# A6SS-4.net
KiCad netlist of a schematic drawn in EAGLE
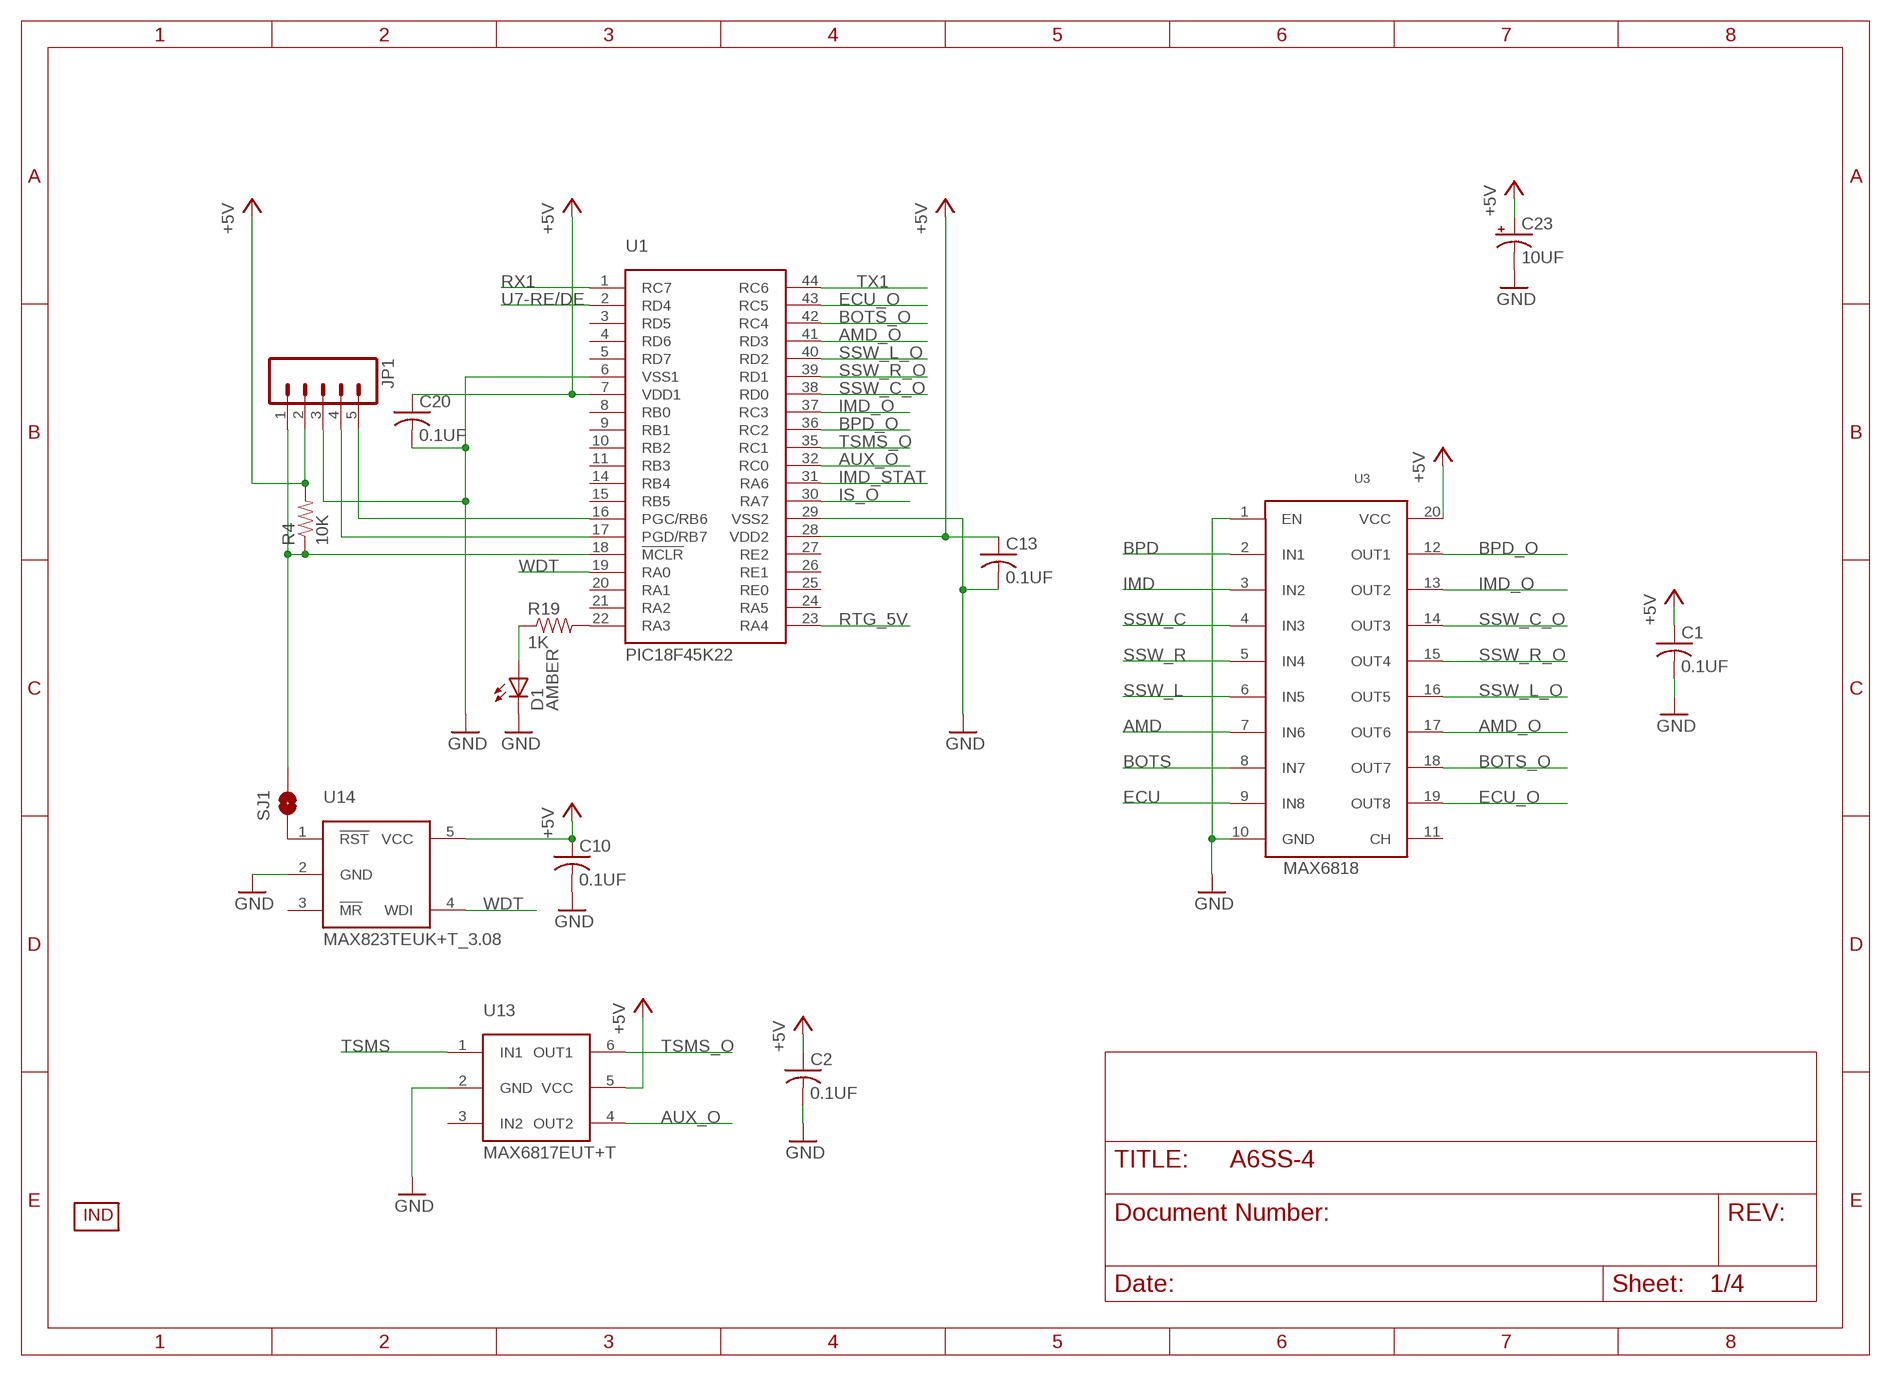
[diagram p0: schematic, sheet 1]
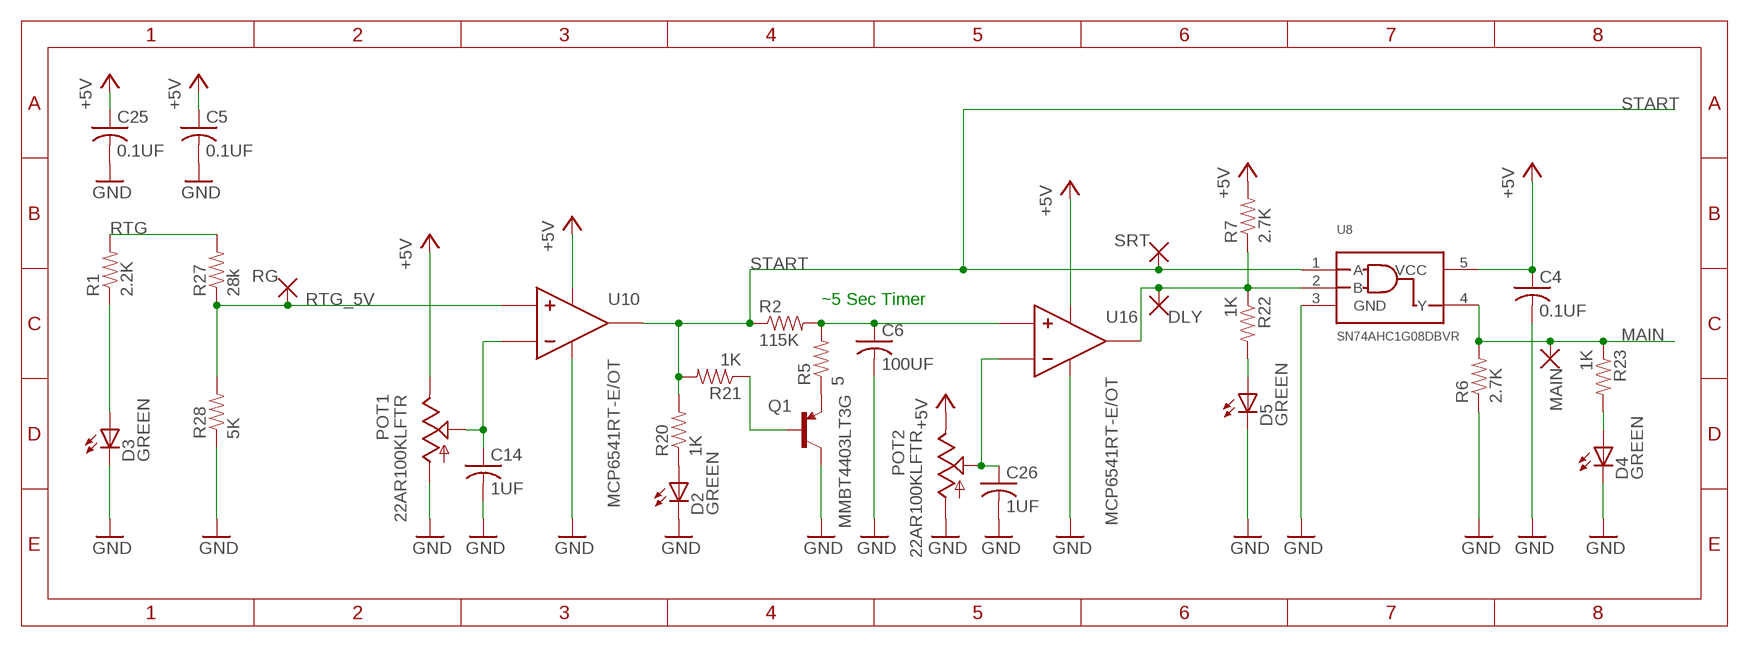
[diagram p1: schematic, sheet 2]
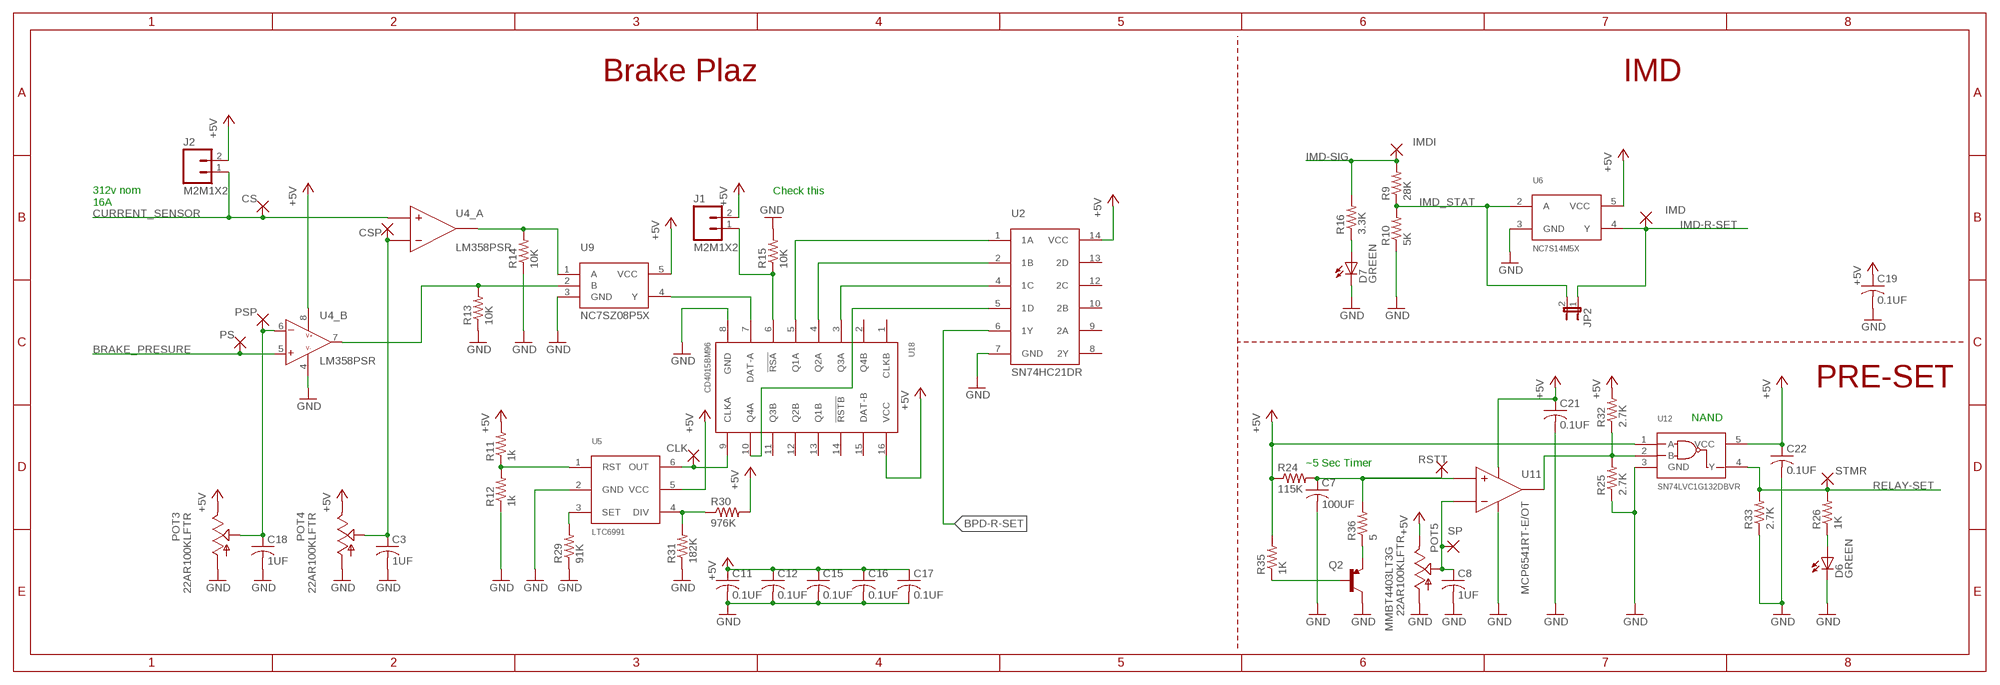
[diagram p2: schematic, sheet 3]
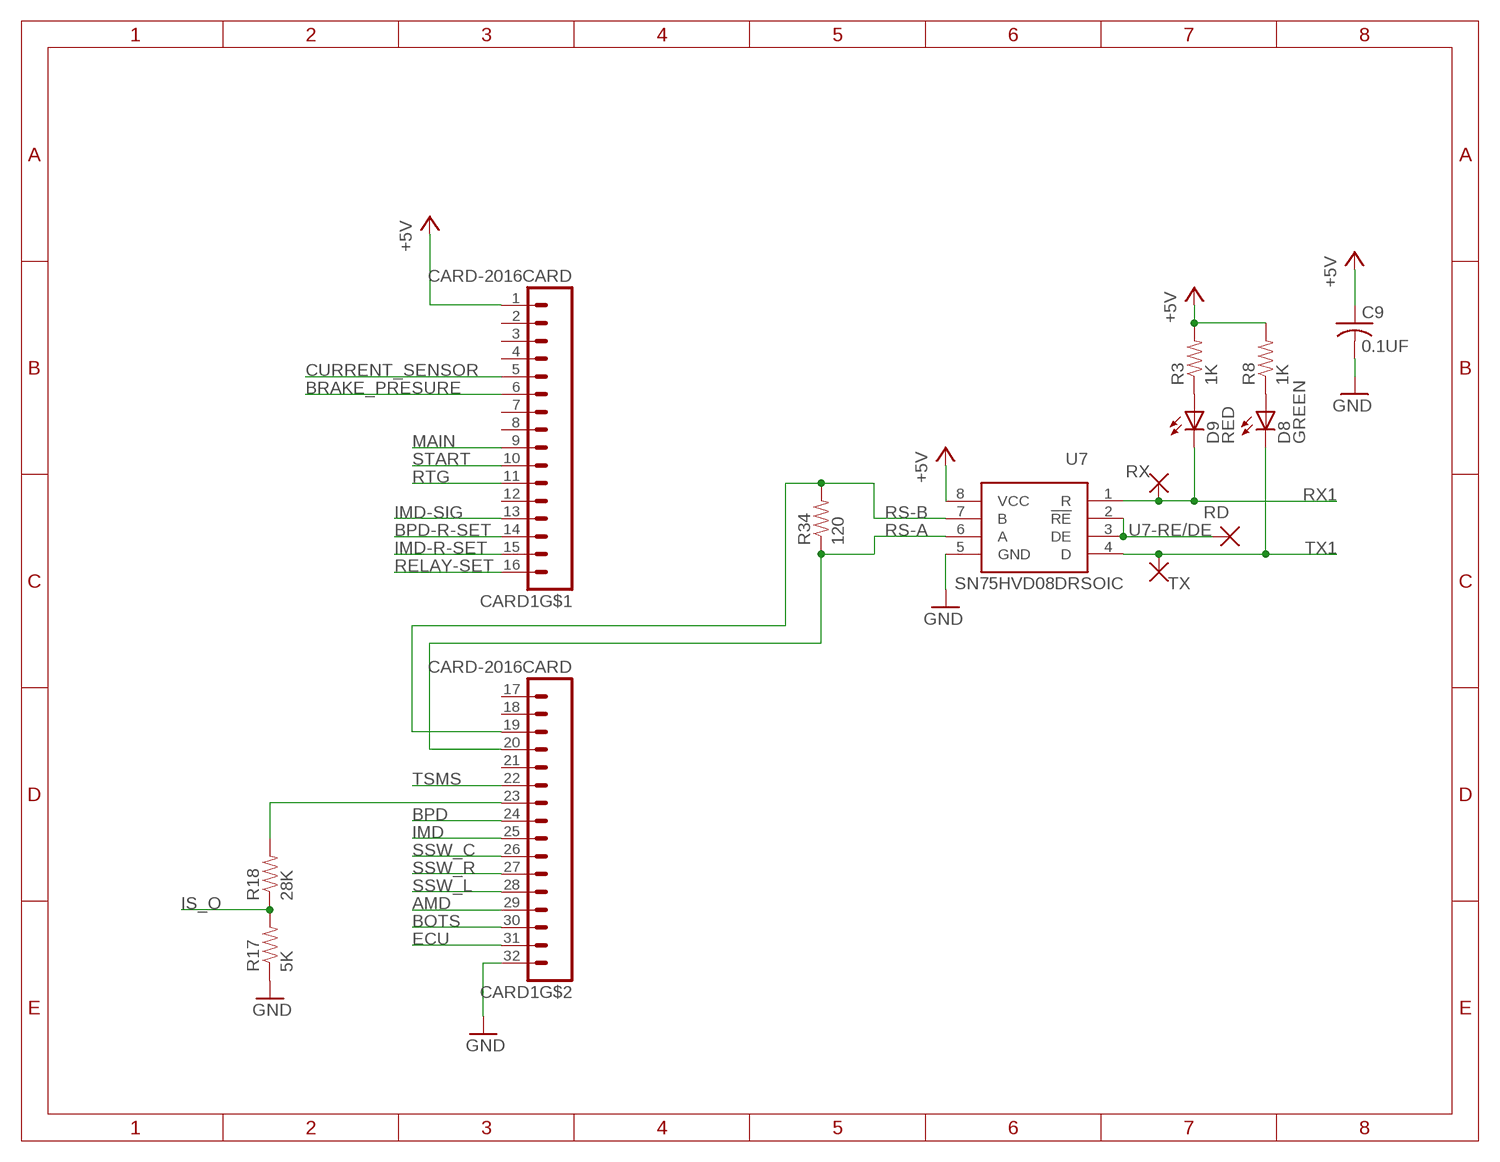
[diagram p3: schematic, sheet 4]

(export (version "E")
  (design (tool "Eeschema 10.0.6"))
  (components
    (comp (ref "C4")
      (value "0.1UF")
      (footprint "eagle-import:0805")
      (fields (field (name "PARTNO") "CC0805ZRY5V9BB104"))
      (libsource (lib "eagle-import") (part "CAP_0.1UF_50V_0805"))
    )
    (comp (ref "C5")
      (value "0.1UF")
      (footprint "eagle-import:0805")
      (fields (field (name "PARTNO") "CC0805ZRY5V9BB104"))
      (libsource (lib "eagle-import") (part "CAP_0.1UF_50V_0805"))
    )
    (comp (ref "C6")
      (value "100UF")
      (footprint "eagle-import:1206")
      (fields (field (name "PARTNO") "GRM31CR60J107ME39K"))
      (libsource (lib "eagle-import") (part "CAP_100UF_6.3V"))
    )
    (comp (ref "C14")
      (value "1UF")
      (footprint "eagle-import:0805")
      (fields (field (name "PARTNO") "UMK212F105ZG-T"))
      (libsource (lib "eagle-import") (part "CAP_1UF_50V_0805"))
    )
    (comp (ref "C25")
      (value "0.1UF")
      (footprint "eagle-import:0805")
      (fields (field (name "PARTNO") "CC0805ZRY5V9BB104"))
      (libsource (lib "eagle-import") (part "CAP_0.1UF_50V_0805"))
    )
    (comp (ref "C26")
      (value "1UF")
      (footprint "eagle-import:0805")
      (fields (field (name "PARTNO") "UMK212F105ZG-T"))
      (libsource (lib "eagle-import") (part "CAP_1UF_50V_0805"))
    )
    (comp (ref "D2")
      (value "GREEN")
      (footprint "eagle-import:CHIP_LED0805")
      (fields (field (name "PARTNO") "LTST-S220GKT"))
      (libsource (lib "eagle-import") (part "LED_GREEN"))
    )
    (comp (ref "D3")
      (value "GREEN")
      (footprint "eagle-import:CHIP_LED0805")
      (fields (field (name "PARTNO") "LTST-S220GKT"))
      (libsource (lib "eagle-import") (part "LED_GREEN"))
    )
    (comp (ref "D4")
      (value "GREEN")
      (footprint "eagle-import:CHIP_LED0805")
      (fields (field (name "PARTNO") "LTST-S220GKT"))
      (libsource (lib "eagle-import") (part "LED_GREEN"))
    )
    (comp (ref "D5")
      (value "GREEN")
      (footprint "eagle-import:CHIP_LED0805")
      (fields (field (name "PARTNO") "LTST-S220GKT"))
      (libsource (lib "eagle-import") (part "LED_GREEN"))
    )
    (comp (ref "DLY")
      (value "TP")
      (footprint "eagle-import:0603")
      (fields (field (name "PARTNO") "1625854-3"))
      (libsource (lib "eagle-import") (part "TP"))
    )
    (comp (ref "MAIN")
      (value "TP")
      (footprint "eagle-import:0603")
      (fields (field (name "PARTNO") "1625854-3"))
      (libsource (lib "eagle-import") (part "TP"))
    )
    (comp (ref "POT1")
      (value "22AR100KLFTR")
      (footprint "eagle-import:22AR100KLFTR")
      (libsource (lib "eagle-import") (part "22AR100KLFTR"))
    )
    (comp (ref "POT2")
      (value "22AR100KLFTR")
      (footprint "eagle-import:22AR100KLFTR")
      (libsource (lib "eagle-import") (part "22AR100KLFTR"))
    )
    (comp (ref "Q1")
      (value "MMBT4403LT3G")
      (footprint "eagle-import:SOT23")
      (libsource (lib "eagle-import") (part "PNP_MMBT4403LT3G"))
    )
    (comp (ref "R1")
      (value "2.2K")
      (footprint "eagle-import:0805")
      (fields (field (name "PARTNO") "RC0805FR-072K2L"))
      (libsource (lib "eagle-import") (part "RES_2.2K_1%_0805"))
    )
    (comp (ref "R2")
      (value "115K")
      (footprint "eagle-import:0805")
      (fields (field (name "PARTNO") "RC0805FR-07115KL"))
      (libsource (lib "eagle-import") (part "RES_115K_1%_0805"))
    )
    (comp (ref "R5")
      (value "5")
      (footprint "eagle-import:0805")
      (fields (field (name "PARTNO") " RC0805JR-075R1L"))
      (libsource (lib "eagle-import") (part "RES_5_5%_0805"))
    )
    (comp (ref "R6")
      (value "2.7K")
      (footprint "eagle-import:0805")
      (fields (field (name "PARTNO") "RC0805JR-072K7L"))
      (libsource (lib "eagle-import") (part "RES_2.7K_5%_0805"))
    )
    (comp (ref "R7")
      (value "2.7K")
      (footprint "eagle-import:0805")
      (fields (field (name "PARTNO") "RC0805JR-072K7L"))
      (libsource (lib "eagle-import") (part "RES_2.7K_5%_0805"))
    )
    (comp (ref "R20")
      (value "1K")
      (footprint "eagle-import:0805")
      (fields (field (name "PARTNO") "RC0805FR-071KL"))
      (libsource (lib "eagle-import") (part "RES_1K_1%_0805"))
    )
    (comp (ref "R21")
      (value "1K")
      (footprint "eagle-import:0805")
      (fields (field (name "PARTNO") "RC0805FR-071KL"))
      (libsource (lib "eagle-import") (part "RES_1K_1%_0805"))
    )
    (comp (ref "R22")
      (value "1K")
      (footprint "eagle-import:0805")
      (fields (field (name "PARTNO") "RC0805FR-071KL"))
      (libsource (lib "eagle-import") (part "RES_1K_1%_0805"))
    )
    (comp (ref "R23")
      (value "1K")
      (footprint "eagle-import:0805")
      (fields (field (name "PARTNO") "RC0805FR-071KL"))
      (libsource (lib "eagle-import") (part "RES_1K_1%_0805"))
    )
    (comp (ref "R27")
      (value "28k")
      (footprint "eagle-import:0805")
      (fields (field (name "PARTNO") "RC0805FR-0728KL"))
      (libsource (lib "eagle-import") (part "RES_28K_1%"))
    )
    (comp (ref "R28")
      (value "5K")
      (footprint "eagle-import:0805")
      (fields (field (name "PARTNO") "PNM0805E5001BST5"))
      (libsource (lib "eagle-import") (part "RES_5K_0.1%"))
    )
    (comp (ref "RG")
      (value "TP")
      (footprint "eagle-import:0603")
      (fields (field (name "PARTNO") "1625854-3"))
      (libsource (lib "eagle-import") (part "TP"))
    )
    (comp (ref "SRT")
      (value "TP")
      (footprint "eagle-import:0603")
      (fields (field (name "PARTNO") "1625854-3"))
      (libsource (lib "eagle-import") (part "TP"))
    )
    (comp (ref "U8")
      (value "SN74AHC1G08DBVR")
      (footprint "eagle-import:SOT23-5")
      (fields (field (name "PARTNO") " SN74AHC1G08DBVR"))
      (libsource (lib "eagle-import") (part "SN74AHC1G08DBVR"))
    )
    (comp (ref "U10")
      (value "MCP6541RT-E/OT")
      (footprint "eagle-import:SOT23-5")
      (libsource (lib "eagle-import") (part "MCP6541RT-E/OT"))
    )
    (comp (ref "U16")
      (value "MCP6541RT-E/OT")
      (footprint "eagle-import:SOT23-5")
      (libsource (lib "eagle-import") (part "MCP6541RT-E/OT"))
    )
    (comp (ref "C9")
      (value "0.1UF")
      (footprint "eagle-import:0805")
      (fields (field (name "PARTNO") "CC0805ZRY5V9BB104"))
      (libsource (lib "eagle-import") (part "CAP_0.1UF_50V_0805"))
    )
    (comp (ref "CARD1")
      (value "CARD-2016CARD")
      (footprint "eagle-import:CARD-2016")
      (libsource (lib "eagle-import") (part "CARD-2016CARD"))
    )
    (comp (ref "D8")
      (value "GREEN")
      (footprint "eagle-import:CHIP_LED0805")
      (fields (field (name "PARTNO") "LTST-S220GKT"))
      (libsource (lib "eagle-import") (part "LED_GREEN"))
    )
    (comp (ref "D9")
      (value "RED")
      (footprint "eagle-import:CHIP_LED0805")
      (fields (field (name "PARTNO") "LH R974-LP-1"))
      (libsource (lib "eagle-import") (part "LED_RED"))
    )
    (comp (ref "R3")
      (value "1K")
      (footprint "eagle-import:0805")
      (fields (field (name "PARTNO") "RC0805FR-071KL"))
      (libsource (lib "eagle-import") (part "RES_1K_1%_0805"))
    )
    (comp (ref "R8")
      (value "1K")
      (footprint "eagle-import:0805")
      (fields (field (name "PARTNO") "RC0805FR-071KL"))
      (libsource (lib "eagle-import") (part "RES_1K_1%_0805"))
    )
    (comp (ref "R17")
      (value "5K")
      (footprint "eagle-import:0805")
      (fields (field (name "PARTNO") "PNM0805E5001BST5"))
      (libsource (lib "eagle-import") (part "RES_5K_0.1%"))
    )
    (comp (ref "R18")
      (value "28K")
      (footprint "eagle-import:0805")
      (fields (field (name "PARTNO") "RC0805FR-0728KL"))
      (libsource (lib "eagle-import") (part "RES_28K_1%"))
    )
    (comp (ref "R34")
      (value "120")
      (footprint "eagle-import:0805")
      (fields (field (name "PARTNO") "RC0805FR-07120RL"))
      (libsource (lib "eagle-import") (part "RES_120_1%_0805"))
    )
    (comp (ref "RD")
      (value "TP")
      (footprint "eagle-import:0603")
      (fields (field (name "PARTNO") "1625854-3"))
      (libsource (lib "eagle-import") (part "TP"))
    )
    (comp (ref "RX")
      (value "TP")
      (footprint "eagle-import:0603")
      (fields (field (name "PARTNO") "1625854-3"))
      (libsource (lib "eagle-import") (part "TP"))
    )
    (comp (ref "TX")
      (value "TP")
      (footprint "eagle-import:0603")
      (fields (field (name "PARTNO") "1625854-3"))
      (libsource (lib "eagle-import") (part "TP"))
    )
    (comp (ref "U7")
      (value "SN75HVD08DRSOIC")
      (footprint "eagle-import:SO-8")
      (fields (field (name "PARTNO") "SN75HVD08DR"))
      (libsource (lib "eagle-import") (part "SN75HVD08DRSOIC"))
    )
    (comp (ref "C1")
      (value "0.1UF")
      (footprint "eagle-import:0805")
      (fields (field (name "PARTNO") "CC0805ZRY5V9BB104"))
      (libsource (lib "eagle-import") (part "CAP_0.1UF_50V_0805"))
    )
    (comp (ref "C2")
      (value "0.1UF")
      (footprint "eagle-import:0805")
      (fields (field (name "PARTNO") "CC0805ZRY5V9BB104"))
      (libsource (lib "eagle-import") (part "CAP_0.1UF_50V_0805"))
    )
    (comp (ref "C10")
      (value "0.1UF")
      (footprint "eagle-import:0805")
      (fields (field (name "PARTNO") "CC0805ZRY5V9BB104"))
      (libsource (lib "eagle-import") (part "CAP_0.1UF_50V_0805"))
    )
    (comp (ref "C13")
      (value "0.1UF")
      (footprint "eagle-import:0805")
      (fields (field (name "PARTNO") "CC0805ZRY5V9BB104"))
      (libsource (lib "eagle-import") (part "CAP_0.1UF_50V_0805"))
    )
    (comp (ref "C20")
      (value "0.1UF")
      (footprint "eagle-import:0805")
      (fields (field (name "PARTNO") "CC0805ZRY5V9BB104"))
      (libsource (lib "eagle-import") (part "CAP_0.1UF_50V_0805"))
    )
    (comp (ref "C23")
      (value "10UF")
      (footprint "eagle-import:EIA3216-16V")
      (fields (field (name "PARTNO") "T491A106M016AT"))
      (libsource (lib "eagle-import") (part "CAP-POL_10UF_16V"))
    )
    (comp (ref "D1")
      (value "AMBER")
      (footprint "eagle-import:CHIP_LED0805")
      (fields (field (name "PARTNO") "HSMA-C170"))
      (libsource (lib "eagle-import") (part "LED_AMBER"))
    )
    (comp (ref "JP1")
      (value "M05LOCK_LONGPADS")
      (footprint "eagle-import:1X05_LOCK_LONGPADS")
      (libsource (lib "eagle-import") (part "M05LOCK_LONGPADS"))
    )
    (comp (ref "R4")
      (value "10K")
      (footprint "eagle-import:0805")
      (fields (field (name "PARTNO") "RC0805FR-0710KL"))
      (libsource (lib "eagle-import") (part "RES_10K_1%_0805"))
    )
    (comp (ref "R19")
      (value "1K")
      (footprint "eagle-import:0805")
      (fields (field (name "PARTNO") "RC0805FR-071KL"))
      (libsource (lib "eagle-import") (part "RES_1K_1%_0805"))
    )
    (comp (ref "SJ1")
      (value "SOLDERJUMPERNO")
      (footprint "eagle-import:SJ_2S-NO")
      (libsource (lib "eagle-import") (part "SOLDERJUMPERNO"))
    )
    (comp (ref "U$1")
      (value "INDPK1")
      (footprint "eagle-import:PICKIT-PIN-1")
      (libsource (lib "eagle-import") (part "INDPK1"))
    )
    (comp (ref "U1")
      (value "PIC18F45K22")
      (footprint "eagle-import:TQFP-44")
      (fields (field (name "PARTNO") "PIC18F45K22T-I/PT"))
      (libsource (lib "eagle-import") (part "PIC18F45K22"))
    )
    (comp (ref "U3")
      (value "MAX6818")
      (footprint "eagle-import:SSOP-20")
      (fields (field (name "PARTNO") "MAX6818EAP+"))
      (libsource (lib "eagle-import") (part "MAX6818"))
    )
    (comp (ref "U13")
      (value "MAX6817EUT+T")
      (footprint "eagle-import:SOT23-6")
      (libsource (lib "eagle-import") (part "MAX6817EUT+T"))
    )
    (comp (ref "U14")
      (value "MAX823TEUK+T_3.08")
      (footprint "eagle-import:SOT23-5")
      (fields (field (name "PARTNO") "MAX823TEUK+T"))
      (libsource (lib "eagle-import") (part "MAX823TEUK+T_3.08"))
    )
    (comp (ref "C3")
      (value "1UF")
      (footprint "eagle-import:0805")
      (fields (field (name "PARTNO") "UMK212F105ZG-T"))
      (libsource (lib "eagle-import") (part "CAP_1UF_50V_0805"))
    )
    (comp (ref "C7")
      (value "100UF")
      (footprint "eagle-import:1206")
      (fields (field (name "PARTNO") "GRM31CR60J107ME39K"))
      (libsource (lib "eagle-import") (part "CAP_100UF_6.3V"))
    )
    (comp (ref "C8")
      (value "1UF")
      (footprint "eagle-import:0805")
      (fields (field (name "PARTNO") "UMK212F105ZG-T"))
      (libsource (lib "eagle-import") (part "CAP_1UF_50V_0805"))
    )
    (comp (ref "C11")
      (value "0.1UF")
      (footprint "eagle-import:0805")
      (fields (field (name "PARTNO") "CC0805ZRY5V9BB104"))
      (libsource (lib "eagle-import") (part "CAP_0.1UF_50V_0805"))
    )
    (comp (ref "C12")
      (value "0.1UF")
      (footprint "eagle-import:0805")
      (fields (field (name "PARTNO") "CC0805ZRY5V9BB104"))
      (libsource (lib "eagle-import") (part "CAP_0.1UF_50V_0805"))
    )
    (comp (ref "C15")
      (value "0.1UF")
      (footprint "eagle-import:0805")
      (fields (field (name "PARTNO") "CC0805ZRY5V9BB104"))
      (libsource (lib "eagle-import") (part "CAP_0.1UF_50V_0805"))
    )
    (comp (ref "C16")
      (value "0.1UF")
      (footprint "eagle-import:0805")
      (fields (field (name "PARTNO") "CC0805ZRY5V9BB104"))
      (libsource (lib "eagle-import") (part "CAP_0.1UF_50V_0805"))
    )
    (comp (ref "C17")
      (value "0.1UF")
      (footprint "eagle-import:0805")
      (fields (field (name "PARTNO") "CC0805ZRY5V9BB104"))
      (libsource (lib "eagle-import") (part "CAP_0.1UF_50V_0805"))
    )
    (comp (ref "C18")
      (value "1UF")
      (footprint "eagle-import:0805")
      (fields (field (name "PARTNO") "UMK212F105ZG-T"))
      (libsource (lib "eagle-import") (part "CAP_1UF_50V_0805"))
    )
    (comp (ref "C19")
      (value "0.1UF")
      (footprint "eagle-import:0805")
      (fields (field (name "PARTNO") "CC0805ZRY5V9BB104"))
      (libsource (lib "eagle-import") (part "CAP_0.1UF_50V_0805"))
    )
    (comp (ref "C21")
      (value "0.1UF")
      (footprint "eagle-import:0805")
      (fields (field (name "PARTNO") "CC0805ZRY5V9BB104"))
      (libsource (lib "eagle-import") (part "CAP_0.1UF_50V_0805"))
    )
    (comp (ref "C22")
      (value "0.1UF")
      (footprint "eagle-import:0805")
      (fields (field (name "PARTNO") "CC0805ZRY5V9BB104"))
      (libsource (lib "eagle-import") (part "CAP_0.1UF_50V_0805"))
    )
    (comp (ref "CLK")
      (value "TP")
      (footprint "eagle-import:0603")
      (fields (field (name "PARTNO") "1625854-3"))
      (libsource (lib "eagle-import") (part "TP"))
    )
    (comp (ref "CS")
      (value "TP")
      (footprint "eagle-import:0603")
      (fields (field (name "PARTNO") "1625854-3"))
      (libsource (lib "eagle-import") (part "TP"))
    )
    (comp (ref "CSP")
      (value "TP")
      (footprint "eagle-import:0603")
      (fields (field (name "PARTNO") "1625854-3"))
      (libsource (lib "eagle-import") (part "TP"))
    )
    (comp (ref "D6")
      (value "GREEN")
      (footprint "eagle-import:CHIP_LED0805")
      (fields (field (name "PARTNO") "LTST-S220GKT"))
      (libsource (lib "eagle-import") (part "LED_GREEN"))
    )
    (comp (ref "D7")
      (value "GREEN")
      (footprint "eagle-import:CHIP_LED0805")
      (fields (field (name "PARTNO") "LTST-S220GKT"))
      (libsource (lib "eagle-import") (part "LED_GREEN"))
    )
    (comp (ref "IMD")
      (value "TP")
      (footprint "eagle-import:0603")
      (fields (field (name "PARTNO") "1625854-3"))
      (libsource (lib "eagle-import") (part "TP"))
    )
    (comp (ref "IMDI")
      (value "TP")
      (footprint "eagle-import:0603")
      (fields (field (name "PARTNO") "1625854-3"))
      (libsource (lib "eagle-import") (part "TP"))
    )
    (comp (ref "J1")
      (value "M2M1X2")
      (footprint "eagle-import:MOLEX-1X2")
      (fields (field (name "PARTNO") "0022232021"))
      (libsource (lib "eagle-import") (part "M2M1X2"))
    )
    (comp (ref "J2")
      (value "M2M1X2")
      (footprint "eagle-import:MOLEX-1X2")
      (fields (field (name "PARTNO") "0022232021"))
      (libsource (lib "eagle-import") (part "M2M1X2"))
    )
    (comp (ref "JP2")
      (value "JUMPER-2SMD-NO")
      (footprint "eagle-import:SJ_2S-NO")
      (libsource (lib "eagle-import") (part "JUMPER-2SMD-NO"))
    )
    (comp (ref "POT3")
      (value "22AR100KLFTR")
      (footprint "eagle-import:22AR100KLFTR")
      (libsource (lib "eagle-import") (part "22AR100KLFTR"))
    )
    (comp (ref "POT4")
      (value "22AR100KLFTR")
      (footprint "eagle-import:22AR100KLFTR")
      (libsource (lib "eagle-import") (part "22AR100KLFTR"))
    )
    (comp (ref "POT5")
      (value "22AR100KLFTR")
      (footprint "eagle-import:22AR100KLFTR")
      (libsource (lib "eagle-import") (part "22AR100KLFTR"))
    )
    (comp (ref "PS")
      (value "TP")
      (footprint "eagle-import:0603")
      (fields (field (name "PARTNO") "1625854-3"))
      (libsource (lib "eagle-import") (part "TP"))
    )
    (comp (ref "PSP")
      (value "TP")
      (footprint "eagle-import:0603")
      (fields (field (name "PARTNO") "1625854-3"))
      (libsource (lib "eagle-import") (part "TP"))
    )
    (comp (ref "Q2")
      (value "MMBT4403LT3G")
      (footprint "eagle-import:SOT23")
      (libsource (lib "eagle-import") (part "PNP_MMBT4403LT3G"))
    )
    (comp (ref "R9")
      (value "28K")
      (footprint "eagle-import:0805")
      (fields (field (name "PARTNO") "RC0805FR-0728KL"))
      (libsource (lib "eagle-import") (part "RES_28K_1%"))
    )
    (comp (ref "R10")
      (value "5K")
      (footprint "eagle-import:0805")
      (fields (field (name "PARTNO") "PNM0805E5001BST5"))
      (libsource (lib "eagle-import") (part "RES_5K_0.1%"))
    )
    (comp (ref "R11")
      (value "1k")
      (footprint "eagle-import:0805")
      (fields (field (name "PARTNO") "RC0805FR-071KL"))
      (libsource (lib "eagle-import") (part "RES_1K_1%_0805"))
    )
    (comp (ref "R12")
      (value "1k")
      (footprint "eagle-import:0805")
      (fields (field (name "PARTNO") "RC0805FR-071KL"))
      (libsource (lib "eagle-import") (part "RES_1K_1%_0805"))
    )
    (comp (ref "R13")
      (value "10K")
      (footprint "eagle-import:0805")
      (fields (field (name "PARTNO") "RC0805FR-0710KL"))
      (libsource (lib "eagle-import") (part "RES_10K_1%_0805"))
    )
    (comp (ref "R14")
      (value "10K")
      (footprint "eagle-import:0805")
      (fields (field (name "PARTNO") "RC0805FR-0710KL"))
      (libsource (lib "eagle-import") (part "RES_10K_1%_0805"))
    )
    (comp (ref "R15")
      (value "10K")
      (footprint "eagle-import:0805")
      (fields (field (name "PARTNO") "RC0805FR-0710KL"))
      (libsource (lib "eagle-import") (part "RES_10K_1%_0805"))
    )
    (comp (ref "R16")
      (value "3.3K")
      (footprint "eagle-import:0805")
      (fields (field (name "PARTNO") "RC0805FR-073K3L"))
      (libsource (lib "eagle-import") (part "RES_3.3K_1%_0805"))
    )
    (comp (ref "R24")
      (value "115K")
      (footprint "eagle-import:0805")
      (fields (field (name "PARTNO") "RC0805FR-07115KL"))
      (libsource (lib "eagle-import") (part "RES_115K_1%_0805"))
    )
    (comp (ref "R25")
      (value "2.7K")
      (footprint "eagle-import:0805")
      (fields (field (name "PARTNO") "RC0805JR-072K7L"))
      (libsource (lib "eagle-import") (part "RES_2.7K_5%_0805"))
    )
    (comp (ref "R26")
      (value "1K")
      (footprint "eagle-import:0805")
      (fields (field (name "PARTNO") "RC0805FR-071KL"))
      (libsource (lib "eagle-import") (part "RES_1K_1%_0805"))
    )
    (comp (ref "R29")
      (value "91K")
      (footprint "eagle-import:0805")
      (fields (field (name "PARTNO") "ERJ-6ENF9102V"))
      (libsource (lib "eagle-import") (part "RES_91K_1%_0805"))
    )
    (comp (ref "R30")
      (value "976K")
      (footprint "eagle-import:0805")
      (fields (field (name "PARTNO") "ERA-6AEB9763V"))
      (libsource (lib "eagle-import") (part "RES_976K_0.1%"))
    )
    (comp (ref "R31")
      (value "182K")
      (footprint "eagle-import:0805")
      (fields (field (name "PARTNO") "ERA-6AEB1823V"))
      (libsource (lib "eagle-import") (part "RES_182K_0.1%"))
    )
    (comp (ref "R32")
      (value "2.7K")
      (footprint "eagle-import:0805")
      (fields (field (name "PARTNO") "RC0805JR-072K7L"))
      (libsource (lib "eagle-import") (part "RES_2.7K_5%_0805"))
    )
    (comp (ref "R33")
      (value "2.7K")
      (footprint "eagle-import:0805")
      (fields (field (name "PARTNO") "RC0805JR-072K7L"))
      (libsource (lib "eagle-import") (part "RES_2.7K_5%_0805"))
    )
    (comp (ref "R35")
      (value "1K")
      (footprint "eagle-import:0805")
      (fields (field (name "PARTNO") "RC0805FR-071KL"))
      (libsource (lib "eagle-import") (part "RES_1K_1%_0805"))
    )
    (comp (ref "R36")
      (value "5")
      (footprint "eagle-import:0805")
      (fields (field (name "PARTNO") " RC0805JR-075R1L"))
      (libsource (lib "eagle-import") (part "RES_5_5%_0805"))
    )
    (comp (ref "RSTT")
      (value "TP")
      (footprint "eagle-import:0603")
      (fields (field (name "PARTNO") "1625854-3"))
      (libsource (lib "eagle-import") (part "TP"))
    )
    (comp (ref "SP")
      (value "TP")
      (footprint "eagle-import:0603")
      (fields (field (name "PARTNO") "1625854-3"))
      (libsource (lib "eagle-import") (part "TP"))
    )
    (comp (ref "STMR")
      (value "TP")
      (footprint "eagle-import:0603")
      (fields (field (name "PARTNO") "1625854-3"))
      (libsource (lib "eagle-import") (part "TP"))
    )
    (comp (ref "U2")
      (value "SN74HC21DR")
      (footprint "eagle-import:SO-14")
      (libsource (lib "eagle-import") (part "SN74HC21DR"))
    )
    (comp (ref "U4")
      (value "LM358PSR")
      (footprint "eagle-import:SO-8")
      (libsource (lib "eagle-import") (part "LM358PSR"))
    )
    (comp (ref "U5")
      (value "LTC6991")
      (footprint "eagle-import:TSOT-23-6")
      (fields (field (name "PARTNO") "LTC6991HS6#TRMPBF"))
      (libsource (lib "eagle-import") (part "LTC6991"))
    )
    (comp (ref "U6")
      (value "NC7S14M5X")
      (footprint "eagle-import:SOT23-5")
      (libsource (lib "eagle-import") (part "NC7S14M5X"))
    )
    (comp (ref "U9")
      (value "NC7SZ08P5X")
      (footprint "eagle-import:SC-70-5")
      (libsource (lib "eagle-import") (part "NC7SZ08P5X"))
    )
    (comp (ref "U11")
      (value "MCP6541RT-E/OT")
      (footprint "eagle-import:SOT23-5")
      (libsource (lib "eagle-import") (part "MCP6541RT-E/OT"))
    )
    (comp (ref "U12")
      (value "SN74LVC1G132DBVR")
      (footprint "eagle-import:SOT23-5")
      (libsource (lib "eagle-import") (part "SN74LVC1G132DBVR"))
    )
    (comp (ref "U18")
      (value "CD4015BM96")
      (footprint "eagle-import:SO-16")
      (libsource (lib "eagle-import") (part "CD4015BM96"))
    )
  )
  (nets
    (net (code "1") (name "+5V") (class "Default")
      (node (ref "C1") (pin "1") (pinfunction "+_1") (pintype "passive"))
      (node (ref "C10") (pin "1") (pinfunction "+_1") (pintype "passive"))
      (node (ref "C11") (pin "1") (pinfunction "+_1") (pintype "passive"))
      (node (ref "C12") (pin "1") (pinfunction "+_1") (pintype "passive"))
      (node (ref "C13") (pin "1") (pinfunction "+_1") (pintype "passive"))
      (node (ref "C15") (pin "1") (pinfunction "+_1") (pintype "passive"))
      (node (ref "C16") (pin "1") (pinfunction "+_1") (pintype "passive"))
      (node (ref "C17") (pin "1") (pinfunction "+_1") (pintype "passive"))
      (node (ref "C19") (pin "1") (pinfunction "+_1") (pintype "passive"))
      (node (ref "C2") (pin "1") (pinfunction "+_1") (pintype "passive"))
      (node (ref "C20") (pin "1") (pinfunction "+_1") (pintype "passive"))
      (node (ref "C21") (pin "1") (pinfunction "+_1") (pintype "passive"))
      (node (ref "C22") (pin "1") (pinfunction "+_1") (pintype "passive"))
      (node (ref "C23") (pin "A") (pinfunction "+_A") (pintype "passive"))
      (node (ref "C25") (pin "1") (pinfunction "+_1") (pintype "passive"))
      (node (ref "C4") (pin "1") (pinfunction "+_1") (pintype "passive"))
      (node (ref "C5") (pin "1") (pinfunction "+_1") (pintype "passive"))
      (node (ref "C9") (pin "1") (pinfunction "+_1") (pintype "passive"))
      (node (ref "CARD1") (pin "1") (pinfunction "1_1") (pintype "passive"))
      (node (ref "J1") (pin "2") (pinfunction "2_2") (pintype "passive"))
      (node (ref "J2") (pin "2") (pinfunction "2_2") (pintype "passive"))
      (node (ref "JP1") (pin "2") (pinfunction "2_2") (pintype "passive"))
      (node (ref "POT1") (pin "1") (pinfunction "CCW_1") (pintype "passive"))
      (node (ref "POT2") (pin "1") (pinfunction "CCW_1") (pintype "passive"))
      (node (ref "POT3") (pin "1") (pinfunction "CCW_1") (pintype "passive"))
      (node (ref "POT4") (pin "1") (pinfunction "CCW_1") (pintype "passive"))
      (node (ref "POT5") (pin "1") (pinfunction "CCW_1") (pintype "passive"))
      (node (ref "R11") (pin "2") (pinfunction "2_2") (pintype "passive"))
      (node (ref "R24") (pin "1") (pinfunction "1_1") (pintype "passive"))
      (node (ref "R3") (pin "2") (pinfunction "2_2") (pintype "passive"))
      (node (ref "R30") (pin "2") (pinfunction "2_2") (pintype "passive"))
      (node (ref "R32") (pin "2") (pinfunction "2_2") (pintype "passive"))
      (node (ref "R35") (pin "2") (pinfunction "2_2") (pintype "passive"))
      (node (ref "R4") (pin "2") (pinfunction "2_2") (pintype "passive"))
      (node (ref "R7") (pin "2") (pinfunction "2_2") (pintype "passive"))
      (node (ref "R8") (pin "2") (pinfunction "2_2") (pintype "passive"))
      (node (ref "U1") (pin "28") (pinfunction "VDD2_28") (pintype "bidirectional"))
      (node (ref "U1") (pin "7") (pinfunction "VDD1_7") (pintype "bidirectional"))
      (node (ref "U10") (pin "2") (pinfunction "VDD_2") (pintype "power_in"))
      (node (ref "U11") (pin "2") (pinfunction "VDD_2") (pintype "power_in"))
      (node (ref "U12") (pin "1") (pinfunction "A_1") (pintype "bidirectional"))
      (node (ref "U12") (pin "5") (pinfunction "VCC_5") (pintype "bidirectional"))
      (node (ref "U13") (pin "5") (pinfunction "VCC_5") (pintype "bidirectional"))
      (node (ref "U14") (pin "5") (pinfunction "VCC_5") (pintype "bidirectional"))
      (node (ref "U16") (pin "2") (pinfunction "VDD_2") (pintype "power_in"))
      (node (ref "U18") (pin "16") (pinfunction "VCC_16") (pintype "bidirectional"))
      (node (ref "U2") (pin "14") (pinfunction "VCC_14") (pintype "bidirectional"))
      (node (ref "U3") (pin "20") (pinfunction "VCC_20") (pintype "bidirectional"))
      (node (ref "U4") (pin "8") (pinfunction "V+_8") (pintype "bidirectional"))
      (node (ref "U5") (pin "5") (pinfunction "VCC_5") (pintype "bidirectional"))
      (node (ref "U6") (pin "5") (pinfunction "VCC_5") (pintype "bidirectional"))
      (node (ref "U7") (pin "8") (pinfunction "VCC_8") (pintype "bidirectional"))
      (node (ref "U8") (pin "5") (pinfunction "VCC_5") (pintype "bidirectional"))
      (node (ref "U9") (pin "5") (pinfunction "VCC_5") (pintype "bidirectional"))
    )
    (net (code "2") (name "AMD") (class "Default")
      (node (ref "CARD1") (pin "29") (pinfunction "13_29") (pintype "passive"))
      (node (ref "U3") (pin "7") (pinfunction "IN6_7") (pintype "bidirectional"))
    )
    (net (code "3") (name "AMD_O") (class "Default")
      (node (ref "U1") (pin "41") (pinfunction "RD3_41") (pintype "bidirectional"))
      (node (ref "U3") (pin "17") (pinfunction "OUT6_17") (pintype "bidirectional"))
    )
    (net (code "4") (name "AUX_O") (class "Default")
      (node (ref "U1") (pin "32") (pinfunction "RC0_32") (pintype "bidirectional"))
      (node (ref "U13") (pin "4") (pinfunction "OUT2_4") (pintype "bidirectional"))
    )
    (net (code "5") (name "BOTS") (class "Default")
      (node (ref "CARD1") (pin "30") (pinfunction "14_30") (pintype "passive"))
      (node (ref "U3") (pin "8") (pinfunction "IN7_8") (pintype "bidirectional"))
    )
    (net (code "6") (name "BOTS_O") (class "Default")
      (node (ref "U1") (pin "42") (pinfunction "RC4_42") (pintype "bidirectional"))
      (node (ref "U3") (pin "18") (pinfunction "OUT7_18") (pintype "bidirectional"))
    )
    (net (code "7") (name "BPD") (class "Default")
      (node (ref "CARD1") (pin "24") (pinfunction "8_24") (pintype "passive"))
      (node (ref "U3") (pin "2") (pinfunction "IN1_2") (pintype "bidirectional"))
    )
    (net (code "8") (name "BPD-R-SET") (class "Default")
      (node (ref "CARD1") (pin "14") (pinfunction "14_14") (pintype "passive"))
      (node (ref "U2") (pin "6") (pinfunction "1Y_6") (pintype "bidirectional"))
    )
    (net (code "9") (name "BPD_O") (class "Default")
      (node (ref "U1") (pin "36") (pinfunction "RC2_36") (pintype "bidirectional"))
      (node (ref "U3") (pin "12") (pinfunction "OUT1_12") (pintype "bidirectional"))
    )
    (net (code "10") (name "BRAKE_PRESURE") (class "Default")
      (node (ref "CARD1") (pin "6") (pinfunction "6_6") (pintype "passive"))
      (node (ref "PS") (pin "1") (pinfunction "P$1_1") (pintype "bidirectional"))
      (node (ref "PS") (pin "2") (pinfunction "P$1_2") (pintype "bidirectional"))
      (node (ref "U4") (pin "5") (pinfunction "+_5") (pintype "bidirectional"))
    )
    (net (code "11") (name "CURRENT_SENSOR") (class "Default")
      (node (ref "CARD1") (pin "5") (pinfunction "5_5") (pintype "passive"))
      (node (ref "CS") (pin "1") (pinfunction "P$1_1") (pintype "bidirectional"))
      (node (ref "CS") (pin "2") (pinfunction "P$1_2") (pintype "bidirectional"))
      (node (ref "J2") (pin "1") (pinfunction "1_1") (pintype "passive"))
      (node (ref "U4") (pin "3") (pinfunction "+_3") (pintype "input"))
    )
    (net (code "12") (name "ECU") (class "Default")
      (node (ref "CARD1") (pin "31") (pinfunction "15_31") (pintype "passive"))
      (node (ref "U3") (pin "9") (pinfunction "IN8_9") (pintype "bidirectional"))
    )
    (net (code "13") (name "ECU_O") (class "Default")
      (node (ref "U1") (pin "43") (pinfunction "RC5_43") (pintype "bidirectional"))
      (node (ref "U3") (pin "19") (pinfunction "OUT8_19") (pintype "bidirectional"))
    )
    (net (code "14") (name "GND") (class "Default")
      (node (ref "C1") (pin "2") (pinfunction "-_2") (pintype "passive"))
      (node (ref "C10") (pin "2") (pinfunction "-_2") (pintype "passive"))
      (node (ref "C11") (pin "2") (pinfunction "-_2") (pintype "passive"))
      (node (ref "C12") (pin "2") (pinfunction "-_2") (pintype "passive"))
      (node (ref "C13") (pin "2") (pinfunction "-_2") (pintype "passive"))
      (node (ref "C14") (pin "2") (pinfunction "-_2") (pintype "passive"))
      (node (ref "C15") (pin "2") (pinfunction "-_2") (pintype "passive"))
      (node (ref "C16") (pin "2") (pinfunction "-_2") (pintype "passive"))
      (node (ref "C17") (pin "2") (pinfunction "-_2") (pintype "passive"))
      (node (ref "C18") (pin "2") (pinfunction "-_2") (pintype "passive"))
      (node (ref "C19") (pin "2") (pinfunction "-_2") (pintype "passive"))
      (node (ref "C2") (pin "2") (pinfunction "-_2") (pintype "passive"))
      (node (ref "C20") (pin "2") (pinfunction "-_2") (pintype "passive"))
      (node (ref "C21") (pin "2") (pinfunction "-_2") (pintype "passive"))
      (node (ref "C22") (pin "2") (pinfunction "-_2") (pintype "passive"))
      (node (ref "C23") (pin "C") (pinfunction "-_C") (pintype "passive"))
      (node (ref "C25") (pin "2") (pinfunction "-_2") (pintype "passive"))
      (node (ref "C26") (pin "2") (pinfunction "-_2") (pintype "passive"))
      (node (ref "C3") (pin "2") (pinfunction "-_2") (pintype "passive"))
      (node (ref "C4") (pin "2") (pinfunction "-_2") (pintype "passive"))
      (node (ref "C5") (pin "2") (pinfunction "-_2") (pintype "passive"))
      (node (ref "C6") (pin "2") (pinfunction "-_2") (pintype "passive"))
      (node (ref "C7") (pin "2") (pinfunction "-_2") (pintype "passive"))
      (node (ref "C8") (pin "2") (pinfunction "-_2") (pintype "passive"))
      (node (ref "C9") (pin "2") (pinfunction "-_2") (pintype "passive"))
      (node (ref "CARD1") (pin "32") (pinfunction "16_32") (pintype "passive"))
      (node (ref "D1") (pin "C") (pinfunction "C_C") (pintype "passive"))
      (node (ref "D2") (pin "C") (pinfunction "C_C") (pintype "passive"))
      (node (ref "D3") (pin "C") (pinfunction "C_C") (pintype "passive"))
      (node (ref "D4") (pin "C") (pinfunction "C_C") (pintype "passive"))
      (node (ref "D5") (pin "C") (pinfunction "C_C") (pintype "passive"))
      (node (ref "D6") (pin "C") (pinfunction "C_C") (pintype "passive"))
      (node (ref "D7") (pin "C") (pinfunction "C_C") (pintype "passive"))
      (node (ref "JP1") (pin "3") (pinfunction "3_3") (pintype "passive"))
      (node (ref "POT1") (pin "3") (pinfunction "CW_3") (pintype "passive"))
      (node (ref "POT2") (pin "3") (pinfunction "CW_3") (pintype "passive"))
      (node (ref "POT3") (pin "3") (pinfunction "CW_3") (pintype "passive"))
      (node (ref "POT4") (pin "3") (pinfunction "CW_3") (pintype "passive"))
      (node (ref "POT5") (pin "3") (pinfunction "CW_3") (pintype "passive"))
      (node (ref "Q1") (pin "3") (pinfunction "C_3") (pintype "passive"))
      (node (ref "Q2") (pin "3") (pinfunction "C_3") (pintype "passive"))
      (node (ref "R10") (pin "1") (pinfunction "1_1") (pintype "passive"))
      (node (ref "R12") (pin "1") (pinfunction "1_1") (pintype "passive"))
      (node (ref "R13") (pin "1") (pinfunction "1_1") (pintype "passive"))
      (node (ref "R14") (pin "1") (pinfunction "1_1") (pintype "passive"))
      (node (ref "R15") (pin "2") (pinfunction "2_2") (pintype "passive"))
      (node (ref "R17") (pin "1") (pinfunction "1_1") (pintype "passive"))
      (node (ref "R25") (pin "1") (pinfunction "1_1") (pintype "passive"))
      (node (ref "R28") (pin "1") (pinfunction "1_1") (pintype "passive"))
      (node (ref "R29") (pin "1") (pinfunction "1_1") (pintype "passive"))
      (node (ref "R31") (pin "1") (pinfunction "1_1") (pintype "passive"))
      (node (ref "R33") (pin "1") (pinfunction "1_1") (pintype "passive"))
      (node (ref "R6") (pin "1") (pinfunction "1_1") (pintype "passive"))
      (node (ref "U1") (pin "29") (pinfunction "VSS2_29") (pintype "bidirectional"))
      (node (ref "U1") (pin "6") (pinfunction "VSS1_6") (pintype "bidirectional"))
      (node (ref "U10") (pin "5") (pinfunction "GND_5") (pintype "power_in"))
      (node (ref "U11") (pin "5") (pinfunction "GND_5") (pintype "power_in"))
      (node (ref "U12") (pin "3") (pinfunction "GND_3") (pintype "bidirectional"))
      (node (ref "U13") (pin "2") (pinfunction "GND_2") (pintype "bidirectional"))
      (node (ref "U14") (pin "2") (pinfunction "GND_2") (pintype "bidirectional"))
      (node (ref "U16") (pin "5") (pinfunction "GND_5") (pintype "power_in"))
      (node (ref "U18") (pin "8") (pinfunction "GND_8") (pintype "bidirectional"))
      (node (ref "U2") (pin "7") (pinfunction "GND_7") (pintype "bidirectional"))
      (node (ref "U3") (pin "1") (pinfunction "EN_1") (pintype "bidirectional"))
      (node (ref "U3") (pin "10") (pinfunction "GND_10") (pintype "bidirectional"))
      (node (ref "U4") (pin "4") (pinfunction "V-_4") (pintype "bidirectional"))
      (node (ref "U5") (pin "2") (pinfunction "GND_2") (pintype "bidirectional"))
      (node (ref "U6") (pin "3") (pinfunction "GND_3") (pintype "bidirectional"))
      (node (ref "U7") (pin "5") (pinfunction "GND_5") (pintype "bidirectional"))
      (node (ref "U8") (pin "3") (pinfunction "GND_3") (pintype "bidirectional"))
      (node (ref "U9") (pin "3") (pinfunction "GND_3") (pintype "bidirectional"))
    )
    (net (code "15") (name "IMD") (class "Default")
      (node (ref "CARD1") (pin "25") (pinfunction "9_25") (pintype "passive"))
      (node (ref "U3") (pin "3") (pinfunction "IN2_3") (pintype "bidirectional"))
    )
    (net (code "16") (name "IMD-R-SET") (class "Default")
      (node (ref "CARD1") (pin "15") (pinfunction "15_15") (pintype "passive"))
      (node (ref "IMD") (pin "1") (pinfunction "P$1_1") (pintype "bidirectional"))
      (node (ref "IMD") (pin "2") (pinfunction "P$1_2") (pintype "bidirectional"))
      (node (ref "JP2") (pin "1") (pinfunction "1_1") (pintype "passive"))
      (node (ref "U6") (pin "4") (pinfunction "Y_4") (pintype "bidirectional"))
    )
    (net (code "17") (name "IMD-SIG") (class "Default")
      (node (ref "CARD1") (pin "13") (pinfunction "13_13") (pintype "passive"))
      (node (ref "IMDI") (pin "1") (pinfunction "P$1_1") (pintype "bidirectional"))
      (node (ref "IMDI") (pin "2") (pinfunction "P$1_2") (pintype "bidirectional"))
      (node (ref "R16") (pin "2") (pinfunction "2_2") (pintype "passive"))
      (node (ref "R9") (pin "2") (pinfunction "2_2") (pintype "passive"))
    )
    (net (code "18") (name "IMD_O") (class "Default")
      (node (ref "U1") (pin "37") (pinfunction "RC3_37") (pintype "bidirectional"))
      (node (ref "U3") (pin "13") (pinfunction "OUT2_13") (pintype "bidirectional"))
    )
    (net (code "19") (name "IMD_STAT") (class "Default")
      (node (ref "JP2") (pin "2") (pinfunction "2_2") (pintype "passive"))
      (node (ref "R10") (pin "2") (pinfunction "2_2") (pintype "passive"))
      (node (ref "R9") (pin "1") (pinfunction "1_1") (pintype "passive"))
      (node (ref "U1") (pin "31") (pinfunction "RA6_31") (pintype "bidirectional"))
      (node (ref "U6") (pin "2") (pinfunction "A_2") (pintype "bidirectional"))
    )
    (net (code "20") (name "IS_O") (class "Default")
      (node (ref "R17") (pin "2") (pinfunction "2_2") (pintype "passive"))
      (node (ref "R18") (pin "1") (pinfunction "1_1") (pintype "passive"))
      (node (ref "U1") (pin "30") (pinfunction "RA7_30") (pintype "bidirectional"))
    )
    (net (code "21") (name "MAIN") (class "Default")
      (node (ref "CARD1") (pin "9") (pinfunction "9_9") (pintype "passive"))
      (node (ref "MAIN") (pin "1") (pinfunction "P$1_1") (pintype "bidirectional"))
      (node (ref "MAIN") (pin "2") (pinfunction "P$1_2") (pintype "bidirectional"))
      (node (ref "R23") (pin "1") (pinfunction "1_1") (pintype "passive"))
      (node (ref "R6") (pin "2") (pinfunction "2_2") (pintype "passive"))
      (node (ref "U8") (pin "4") (pinfunction "Y_4") (pintype "bidirectional"))
    )
    (net (code "22") (name "Net-(C3-+)") (class "Default")
      (node (ref "C3") (pin "1") (pinfunction "+_1") (pintype "passive"))
      (node (ref "CSP") (pin "1") (pinfunction "P$1_1") (pintype "bidirectional"))
      (node (ref "CSP") (pin "2") (pinfunction "P$1_2") (pintype "bidirectional"))
      (node (ref "POT4") (pin "2") (pinfunction "W_2") (pintype "passive"))
      (node (ref "U4") (pin "2") (pinfunction "-_2") (pintype "input"))
    )
    (net (code "23") (name "Net-(C6-+)") (class "Default")
      (node (ref "C6") (pin "1") (pinfunction "+_1") (pintype "passive"))
      (node (ref "R2") (pin "2") (pinfunction "2_2") (pintype "passive"))
      (node (ref "R5") (pin "2") (pinfunction "2_2") (pintype "passive"))
      (node (ref "U16") (pin "3") (pinfunction "+_3") (pintype "input"))
    )
    (net (code "24") (name "Net-(C7-+)") (class "Default")
      (node (ref "C7") (pin "1") (pinfunction "+_1") (pintype "passive"))
      (node (ref "R24") (pin "2") (pinfunction "2_2") (pintype "passive"))
      (node (ref "R36") (pin "2") (pinfunction "2_2") (pintype "passive"))
      (node (ref "RSTT") (pin "1") (pinfunction "P$1_1") (pintype "bidirectional"))
      (node (ref "RSTT") (pin "2") (pinfunction "P$1_2") (pintype "bidirectional"))
      (node (ref "U11") (pin "3") (pinfunction "+_3") (pintype "input"))
    )
    (net (code "25") (name "Net-(C8-+)") (class "Default")
      (node (ref "C8") (pin "1") (pinfunction "+_1") (pintype "passive"))
      (node (ref "POT5") (pin "2") (pinfunction "W_2") (pintype "passive"))
      (node (ref "SP") (pin "1") (pinfunction "P$1_1") (pintype "bidirectional"))
      (node (ref "SP") (pin "2") (pinfunction "P$1_2") (pintype "bidirectional"))
      (node (ref "U11") (pin "4") (pinfunction "-_4") (pintype "input"))
    )
    (net (code "26") (name "Net-(C14-+)") (class "Default")
      (node (ref "C14") (pin "1") (pinfunction "+_1") (pintype "passive"))
      (node (ref "POT1") (pin "2") (pinfunction "W_2") (pintype "passive"))
      (node (ref "U10") (pin "4") (pinfunction "-_4") (pintype "input"))
    )
    (net (code "27") (name "Net-(C18-+)") (class "Default")
      (node (ref "C18") (pin "1") (pinfunction "+_1") (pintype "passive"))
      (node (ref "POT3") (pin "2") (pinfunction "W_2") (pintype "passive"))
      (node (ref "PSP") (pin "1") (pinfunction "P$1_1") (pintype "bidirectional"))
      (node (ref "PSP") (pin "2") (pinfunction "P$1_2") (pintype "bidirectional"))
      (node (ref "U4") (pin "6") (pinfunction "-_6") (pintype "bidirectional"))
    )
    (net (code "28") (name "Net-(C26-+)") (class "Default")
      (node (ref "C26") (pin "1") (pinfunction "+_1") (pintype "passive"))
      (node (ref "POT2") (pin "2") (pinfunction "W_2") (pintype "passive"))
      (node (ref "U16") (pin "4") (pinfunction "-_4") (pintype "input"))
    )
    (net (code "29") (name "Net-(CARD1B-7)") (class "Default")
      (node (ref "CARD1") (pin "23") (pinfunction "7_23") (pintype "passive"))
      (node (ref "R18") (pin "2") (pinfunction "2_2") (pintype "passive"))
    )
    (net (code "30") (name "Net-(D1-PadA)") (class "Default")
      (node (ref "D1") (pin "A") (pinfunction "A_A") (pintype "passive"))
      (node (ref "R19") (pin "1") (pinfunction "1_1") (pintype "passive"))
    )
    (net (code "31") (name "Net-(D2-PadA)") (class "Default")
      (node (ref "D2") (pin "A") (pinfunction "A_A") (pintype "passive"))
      (node (ref "R20") (pin "1") (pinfunction "1_1") (pintype "passive"))
    )
    (net (code "32") (name "Net-(D3-PadA)") (class "Default")
      (node (ref "D3") (pin "A") (pinfunction "A_A") (pintype "passive"))
      (node (ref "R1") (pin "1") (pinfunction "1_1") (pintype "passive"))
    )
    (net (code "33") (name "Net-(D4-PadA)") (class "Default")
      (node (ref "D4") (pin "A") (pinfunction "A_A") (pintype "passive"))
      (node (ref "R23") (pin "2") (pinfunction "2_2") (pintype "passive"))
    )
    (net (code "34") (name "Net-(D5-PadA)") (class "Default")
      (node (ref "D5") (pin "A") (pinfunction "A_A") (pintype "passive"))
      (node (ref "R22") (pin "2") (pinfunction "2_2") (pintype "passive"))
    )
    (net (code "35") (name "Net-(D6-PadA)") (class "Default")
      (node (ref "D6") (pin "A") (pinfunction "A_A") (pintype "passive"))
      (node (ref "R26") (pin "1") (pinfunction "1_1") (pintype "passive"))
    )
    (net (code "36") (name "Net-(D7-PadA)") (class "Default")
      (node (ref "D7") (pin "A") (pinfunction "A_A") (pintype "passive"))
      (node (ref "R16") (pin "1") (pinfunction "1_1") (pintype "passive"))
    )
    (net (code "37") (name "Net-(D8-PadA)") (class "Default")
      (node (ref "D8") (pin "A") (pinfunction "A_A") (pintype "passive"))
      (node (ref "R8") (pin "1") (pinfunction "1_1") (pintype "passive"))
    )
    (net (code "38") (name "Net-(D9-PadA)") (class "Default")
      (node (ref "D9") (pin "A") (pinfunction "A_A") (pintype "passive"))
      (node (ref "R3") (pin "1") (pinfunction "1_1") (pintype "passive"))
    )
    (net (code "39") (name "Net-(Q1-B)") (class "Default")
      (node (ref "Q1") (pin "1") (pinfunction "B_1") (pintype "passive"))
      (node (ref "R21") (pin "1") (pinfunction "1_1") (pintype "passive"))
    )
    (net (code "40") (name "Net-(Q1-E)") (class "Default")
      (node (ref "Q1") (pin "2") (pinfunction "E_2") (pintype "passive"))
      (node (ref "R5") (pin "1") (pinfunction "1_1") (pintype "passive"))
    )
    (net (code "41") (name "Net-(Q2-B)") (class "Default")
      (node (ref "Q2") (pin "1") (pinfunction "B_1") (pintype "passive"))
      (node (ref "R35") (pin "1") (pinfunction "1_1") (pintype "passive"))
    )
    (net (code "42") (name "Net-(Q2-E)") (class "Default")
      (node (ref "Q2") (pin "2") (pinfunction "E_2") (pintype "passive"))
      (node (ref "R36") (pin "1") (pinfunction "1_1") (pintype "passive"))
    )
    (net (code "43") (name "Net-(U1-PGC{slash}RB6)") (class "Default")
      (node (ref "JP1") (pin "5") (pinfunction "5_5") (pintype "passive"))
      (node (ref "U1") (pin "16") (pinfunction "PGC/RB6_16") (pintype "bidirectional"))
    )
    (net (code "44") (name "Net-(U1-PGD{slash}RB7)") (class "Default")
      (node (ref "JP1") (pin "4") (pinfunction "4_4") (pintype "passive"))
      (node (ref "U1") (pin "17") (pinfunction "PGD/RB7_17") (pintype "bidirectional"))
    )
    (net (code "45") (name "Net-(U1-RA3)") (class "Default")
      (node (ref "R19") (pin "2") (pinfunction "2_2") (pintype "passive"))
      (node (ref "U1") (pin "22") (pinfunction "RA3_22") (pintype "bidirectional"))
    )
    (net (code "46") (name "Net-(U1-~{MCLR})") (class "Default")
      (node (ref "JP1") (pin "1") (pinfunction "1_1") (pintype "passive"))
      (node (ref "R4") (pin "1") (pinfunction "1_1") (pintype "passive"))
      (node (ref "SJ1") (pin "2") (pinfunction "2_2") (pintype "passive"))
      (node (ref "U1") (pin "18") (pinfunction "~{MCLR}_18") (pintype "bidirectional"))
    )
    (net (code "47") (name "Net-(U4A-VOUT)") (class "Default")
      (node (ref "R14") (pin "2") (pinfunction "2_2") (pintype "passive"))
      (node (ref "U4") (pin "1") (pinfunction "VOUT_1") (pintype "output"))
      (node (ref "U9") (pin "1") (pinfunction "A_1") (pintype "bidirectional"))
    )
    (net (code "48") (name "Net-(U4B-O)") (class "Default")
      (node (ref "R13") (pin "2") (pinfunction "2_2") (pintype "passive"))
      (node (ref "U4") (pin "7") (pinfunction "O_7") (pintype "bidirectional"))
      (node (ref "U9") (pin "2") (pinfunction "B_2") (pintype "bidirectional"))
    )
    (net (code "49") (name "Net-(U5-DIV)") (class "Default")
      (node (ref "R30") (pin "1") (pinfunction "1_1") (pintype "passive"))
      (node (ref "R31") (pin "2") (pinfunction "2_2") (pintype "passive"))
      (node (ref "U5") (pin "4") (pinfunction "DIV_4") (pintype "bidirectional"))
    )
    (net (code "50") (name "Net-(U5-RST)") (class "Default")
      (node (ref "R11") (pin "1") (pinfunction "1_1") (pintype "passive"))
      (node (ref "R12") (pin "2") (pinfunction "2_2") (pintype "passive"))
      (node (ref "U5") (pin "1") (pinfunction "RST_1") (pintype "bidirectional"))
    )
    (net (code "51") (name "Net-(U5-SET)") (class "Default")
      (node (ref "R29") (pin "2") (pinfunction "2_2") (pintype "passive"))
      (node (ref "U5") (pin "3") (pinfunction "SET_3") (pintype "bidirectional"))
    )
    (net (code "52") (name "Net-(U11-VOUT)") (class "Default")
      (node (ref "R25") (pin "2") (pinfunction "2_2") (pintype "passive"))
      (node (ref "R32") (pin "1") (pinfunction "1_1") (pintype "passive"))
      (node (ref "U11") (pin "1") (pinfunction "VOUT_1") (pintype "output"))
      (node (ref "U12") (pin "2") (pinfunction "B_2") (pintype "bidirectional"))
    )
    (net (code "53") (name "Net-(U14-~{RST})") (class "Default")
      (node (ref "SJ1") (pin "1") (pinfunction "1_1") (pintype "passive"))
      (node (ref "U14") (pin "1") (pinfunction "~{RST}_1") (pintype "bidirectional"))
    )
    (net (code "54") (name "Net-(U16-VOUT)") (class "Default")
      (node (ref "DLY") (pin "1") (pinfunction "P$1_1") (pintype "bidirectional"))
      (node (ref "DLY") (pin "2") (pinfunction "P$1_2") (pintype "bidirectional"))
      (node (ref "R22") (pin "1") (pinfunction "1_1") (pintype "passive"))
      (node (ref "R7") (pin "1") (pinfunction "1_1") (pintype "passive"))
      (node (ref "U16") (pin "1") (pinfunction "VOUT_1") (pintype "output"))
      (node (ref "U8") (pin "2") (pinfunction "B_2") (pintype "bidirectional"))
    )
    (net (code "55") (name "Net-(U18-CLKA)") (class "Default")
      (node (ref "CLK") (pin "1") (pinfunction "P$1_1") (pintype "bidirectional"))
      (node (ref "CLK") (pin "2") (pinfunction "P$1_2") (pintype "bidirectional"))
      (node (ref "U18") (pin "9") (pinfunction "CLKA_9") (pintype "bidirectional"))
      (node (ref "U5") (pin "6") (pinfunction "OUT_6") (pintype "bidirectional"))
    )
    (net (code "56") (name "Net-(U18-DAT-A)") (class "Default")
      (node (ref "U18") (pin "7") (pinfunction "DAT-A_7") (pintype "bidirectional"))
      (node (ref "U9") (pin "4") (pinfunction "Y_4") (pintype "bidirectional"))
    )
    (net (code "57") (name "Net-(U18-Q1A)") (class "Default")
      (node (ref "U18") (pin "5") (pinfunction "Q1A_5") (pintype "bidirectional"))
      (node (ref "U2") (pin "1") (pinfunction "1A_1") (pintype "bidirectional"))
    )
    (net (code "58") (name "Net-(U18-Q2A)") (class "Default")
      (node (ref "U18") (pin "4") (pinfunction "Q2A_4") (pintype "bidirectional"))
      (node (ref "U2") (pin "2") (pinfunction "1B_2") (pintype "bidirectional"))
    )
    (net (code "59") (name "Net-(U18-Q3A)") (class "Default")
      (node (ref "U18") (pin "3") (pinfunction "Q3A_3") (pintype "bidirectional"))
      (node (ref "U2") (pin "4") (pinfunction "1C_4") (pintype "bidirectional"))
    )
    (net (code "60") (name "Net-(U18-Q4A)") (class "Default")
      (node (ref "U18") (pin "10") (pinfunction "Q4A_10") (pintype "bidirectional"))
      (node (ref "U2") (pin "5") (pinfunction "1D_5") (pintype "bidirectional"))
    )
    (net (code "61") (name "Net-(U18-~{RSA})") (class "Default")
      (node (ref "J1") (pin "1") (pinfunction "1_1") (pintype "passive"))
      (node (ref "R15") (pin "1") (pinfunction "1_1") (pintype "passive"))
      (node (ref "U18") (pin "6") (pinfunction "~{RSA}_6") (pintype "bidirectional"))
    )
    (net (code "62") (name "RELAY-SET") (class "Default")
      (node (ref "CARD1") (pin "16") (pinfunction "16_16") (pintype "passive"))
      (node (ref "R26") (pin "2") (pinfunction "2_2") (pintype "passive"))
      (node (ref "R33") (pin "2") (pinfunction "2_2") (pintype "passive"))
      (node (ref "STMR") (pin "1") (pinfunction "P$1_1") (pintype "bidirectional"))
      (node (ref "STMR") (pin "2") (pinfunction "P$1_2") (pintype "bidirectional"))
      (node (ref "U12") (pin "4") (pinfunction "Y_4") (pintype "bidirectional"))
    )
    (net (code "63") (name "RS-A") (class "Default")
      (node (ref "CARD1") (pin "20") (pinfunction "4_20") (pintype "passive"))
      (node (ref "R34") (pin "1") (pinfunction "1_1") (pintype "passive"))
      (node (ref "U7") (pin "6") (pinfunction "A_6") (pintype "bidirectional"))
    )
    (net (code "64") (name "RS-B") (class "Default")
      (node (ref "CARD1") (pin "19") (pinfunction "3_19") (pintype "passive"))
      (node (ref "R34") (pin "2") (pinfunction "2_2") (pintype "passive"))
      (node (ref "U7") (pin "7") (pinfunction "B_7") (pintype "bidirectional"))
    )
    (net (code "65") (name "RTG") (class "Default")
      (node (ref "CARD1") (pin "11") (pinfunction "11_11") (pintype "passive"))
      (node (ref "R1") (pin "2") (pinfunction "2_2") (pintype "passive"))
      (node (ref "R27") (pin "2") (pinfunction "2_2") (pintype "passive"))
    )
    (net (code "66") (name "RTG_5V") (class "Default")
      (node (ref "R27") (pin "1") (pinfunction "1_1") (pintype "passive"))
      (node (ref "R28") (pin "2") (pinfunction "2_2") (pintype "passive"))
      (node (ref "RG") (pin "1") (pinfunction "P$1_1") (pintype "bidirectional"))
      (node (ref "RG") (pin "2") (pinfunction "P$1_2") (pintype "bidirectional"))
      (node (ref "U1") (pin "23") (pinfunction "RA4_23") (pintype "bidirectional"))
      (node (ref "U10") (pin "3") (pinfunction "+_3") (pintype "input"))
    )
    (net (code "67") (name "RX1") (class "Default")
      (node (ref "D9") (pin "C") (pinfunction "C_C") (pintype "passive"))
      (node (ref "RX") (pin "1") (pinfunction "P$1_1") (pintype "bidirectional"))
      (node (ref "RX") (pin "2") (pinfunction "P$1_2") (pintype "bidirectional"))
      (node (ref "U1") (pin "1") (pinfunction "RC7_1") (pintype "bidirectional"))
      (node (ref "U7") (pin "1") (pinfunction "R_1") (pintype "bidirectional"))
    )
    (net (code "68") (name "SSW_C") (class "Default")
      (node (ref "CARD1") (pin "26") (pinfunction "10_26") (pintype "passive"))
      (node (ref "U3") (pin "4") (pinfunction "IN3_4") (pintype "bidirectional"))
    )
    (net (code "69") (name "SSW_C_O") (class "Default")
      (node (ref "U1") (pin "38") (pinfunction "RD0_38") (pintype "bidirectional"))
      (node (ref "U3") (pin "14") (pinfunction "OUT3_14") (pintype "bidirectional"))
    )
    (net (code "70") (name "SSW_L") (class "Default")
      (node (ref "CARD1") (pin "28") (pinfunction "12_28") (pintype "passive"))
      (node (ref "U3") (pin "6") (pinfunction "IN5_6") (pintype "bidirectional"))
    )
    (net (code "71") (name "SSW_L_O") (class "Default")
      (node (ref "U1") (pin "40") (pinfunction "RD2_40") (pintype "bidirectional"))
      (node (ref "U3") (pin "16") (pinfunction "OUT5_16") (pintype "bidirectional"))
    )
    (net (code "72") (name "SSW_R") (class "Default")
      (node (ref "CARD1") (pin "27") (pinfunction "11_27") (pintype "passive"))
      (node (ref "U3") (pin "5") (pinfunction "IN4_5") (pintype "bidirectional"))
    )
    (net (code "73") (name "SSW_R_O") (class "Default")
      (node (ref "U1") (pin "39") (pinfunction "RD1_39") (pintype "bidirectional"))
      (node (ref "U3") (pin "15") (pinfunction "OUT4_15") (pintype "bidirectional"))
    )
    (net (code "74") (name "START") (class "Default")
      (node (ref "CARD1") (pin "10") (pinfunction "10_10") (pintype "passive"))
      (node (ref "R2") (pin "1") (pinfunction "1_1") (pintype "passive"))
      (node (ref "R20") (pin "2") (pinfunction "2_2") (pintype "passive"))
      (node (ref "R21") (pin "2") (pinfunction "2_2") (pintype "passive"))
      (node (ref "SRT") (pin "1") (pinfunction "P$1_1") (pintype "bidirectional"))
      (node (ref "SRT") (pin "2") (pinfunction "P$1_2") (pintype "bidirectional"))
      (node (ref "U10") (pin "1") (pinfunction "VOUT_1") (pintype "output"))
      (node (ref "U8") (pin "1") (pinfunction "A_1") (pintype "bidirectional"))
    )
    (net (code "75") (name "TSMS") (class "Default")
      (node (ref "CARD1") (pin "22") (pinfunction "6_22") (pintype "passive"))
      (node (ref "U13") (pin "1") (pinfunction "IN1_1") (pintype "bidirectional"))
    )
    (net (code "76") (name "TSMS_O") (class "Default")
      (node (ref "U1") (pin "35") (pinfunction "RC1_35") (pintype "bidirectional"))
      (node (ref "U13") (pin "6") (pinfunction "OUT1_6") (pintype "bidirectional"))
    )
    (net (code "77") (name "TX1") (class "Default")
      (node (ref "D8") (pin "C") (pinfunction "C_C") (pintype "passive"))
      (node (ref "TX") (pin "1") (pinfunction "P$1_1") (pintype "bidirectional"))
      (node (ref "TX") (pin "2") (pinfunction "P$1_2") (pintype "bidirectional"))
      (node (ref "U1") (pin "44") (pinfunction "RC6_44") (pintype "bidirectional"))
      (node (ref "U7") (pin "4") (pinfunction "D_4") (pintype "bidirectional"))
    )
    (net (code "78") (name "U7-RE{slash}DE") (class "Default")
      (node (ref "RD") (pin "1") (pinfunction "P$1_1") (pintype "bidirectional"))
      (node (ref "RD") (pin "2") (pinfunction "P$1_2") (pintype "bidirectional"))
      (node (ref "U1") (pin "2") (pinfunction "RD4_2") (pintype "bidirectional"))
      (node (ref "U7") (pin "2") (pinfunction "~{RE}_2") (pintype "bidirectional"))
      (node (ref "U7") (pin "3") (pinfunction "DE_3") (pintype "bidirectional"))
    )
    (net (code "79") (name "WDT") (class "Default")
      (node (ref "U1") (pin "19") (pinfunction "RA0_19") (pintype "bidirectional"))
      (node (ref "U14") (pin "4") (pinfunction "WDI_4") (pintype "bidirectional"))
    )
    (net (code "80") (name "unconnected-(CARD1-Pad2)") (class "Default")
      (node (ref "CARD1") (pin "2") (pinfunction "2_2") (pintype "passive"))
    )
    (net (code "81") (name "unconnected-(CARD1-Pad3)") (class "Default")
      (node (ref "CARD1") (pin "3") (pinfunction "3_3") (pintype "passive"))
    )
    (net (code "82") (name "unconnected-(CARD1-Pad4)") (class "Default")
      (node (ref "CARD1") (pin "4") (pinfunction "4_4") (pintype "passive"))
    )
    (net (code "83") (name "unconnected-(CARD1-Pad7)") (class "Default")
      (node (ref "CARD1") (pin "7") (pinfunction "7_7") (pintype "passive"))
    )
    (net (code "84") (name "unconnected-(CARD1-Pad8)") (class "Default")
      (node (ref "CARD1") (pin "8") (pinfunction "8_8") (pintype "passive"))
    )
    (net (code "85") (name "unconnected-(CARD1-Pad12)") (class "Default")
      (node (ref "CARD1") (pin "12") (pinfunction "12_12") (pintype "passive"))
    )
    (net (code "86") (name "unconnected-(CARD1B-1-Pad17)") (class "Default")
      (node (ref "CARD1") (pin "17") (pinfunction "1_17") (pintype "passive"))
    )
    (net (code "87") (name "unconnected-(CARD1B-2-Pad18)") (class "Default")
      (node (ref "CARD1") (pin "18") (pinfunction "2_18") (pintype "passive"))
    )
    (net (code "88") (name "unconnected-(CARD1B-5-Pad21)") (class "Default")
      (node (ref "CARD1") (pin "21") (pinfunction "5_21") (pintype "passive"))
    )
    (net (code "89") (name "unconnected-(U1-RA1-Pad20)") (class "Default")
      (node (ref "U1") (pin "20") (pinfunction "RA1_20") (pintype "bidirectional"))
    )
    (net (code "90") (name "unconnected-(U1-RA2-Pad21)") (class "Default")
      (node (ref "U1") (pin "21") (pinfunction "RA2_21") (pintype "bidirectional"))
    )
    (net (code "91") (name "unconnected-(U1-RA5-Pad24)") (class "Default")
      (node (ref "U1") (pin "24") (pinfunction "RA5_24") (pintype "bidirectional"))
    )
    (net (code "92") (name "unconnected-(U1-RB0-Pad8)") (class "Default")
      (node (ref "U1") (pin "8") (pinfunction "RB0_8") (pintype "bidirectional"))
    )
    (net (code "93") (name "unconnected-(U1-RB1-Pad9)") (class "Default")
      (node (ref "U1") (pin "9") (pinfunction "RB1_9") (pintype "bidirectional"))
    )
    (net (code "94") (name "unconnected-(U1-RB2-Pad10)") (class "Default")
      (node (ref "U1") (pin "10") (pinfunction "RB2_10") (pintype "bidirectional"))
    )
    (net (code "95") (name "unconnected-(U1-RB3-Pad11)") (class "Default")
      (node (ref "U1") (pin "11") (pinfunction "RB3_11") (pintype "bidirectional"))
    )
    (net (code "96") (name "unconnected-(U1-RB4-Pad14)") (class "Default")
      (node (ref "U1") (pin "14") (pinfunction "RB4_14") (pintype "bidirectional"))
    )
    (net (code "97") (name "unconnected-(U1-RB5-Pad15)") (class "Default")
      (node (ref "U1") (pin "15") (pinfunction "RB5_15") (pintype "bidirectional"))
    )
    (net (code "98") (name "unconnected-(U1-RD5-Pad3)") (class "Default")
      (node (ref "U1") (pin "3") (pinfunction "RD5_3") (pintype "bidirectional"))
    )
    (net (code "99") (name "unconnected-(U1-RD6-Pad4)") (class "Default")
      (node (ref "U1") (pin "4") (pinfunction "RD6_4") (pintype "bidirectional"))
    )
    (net (code "100") (name "unconnected-(U1-RD7-Pad5)") (class "Default")
      (node (ref "U1") (pin "5") (pinfunction "RD7_5") (pintype "bidirectional"))
    )
    (net (code "101") (name "unconnected-(U1-RE0-Pad25)") (class "Default")
      (node (ref "U1") (pin "25") (pinfunction "RE0_25") (pintype "bidirectional"))
    )
    (net (code "102") (name "unconnected-(U1-RE1-Pad26)") (class "Default")
      (node (ref "U1") (pin "26") (pinfunction "RE1_26") (pintype "bidirectional"))
    )
    (net (code "103") (name "unconnected-(U1-RE2-Pad27)") (class "Default")
      (node (ref "U1") (pin "27") (pinfunction "RE2_27") (pintype "bidirectional"))
    )
    (net (code "104") (name "unconnected-(U2-2A-Pad9)") (class "Default")
      (node (ref "U2") (pin "9") (pinfunction "2A_9") (pintype "bidirectional"))
    )
    (net (code "105") (name "unconnected-(U2-2B-Pad10)") (class "Default")
      (node (ref "U2") (pin "10") (pinfunction "2B_10") (pintype "bidirectional"))
    )
    (net (code "106") (name "unconnected-(U2-2C-Pad12)") (class "Default")
      (node (ref "U2") (pin "12") (pinfunction "2C_12") (pintype "bidirectional"))
    )
    (net (code "107") (name "unconnected-(U2-2D-Pad13)") (class "Default")
      (node (ref "U2") (pin "13") (pinfunction "2D_13") (pintype "bidirectional"))
    )
    (net (code "108") (name "unconnected-(U2-2Y-Pad8)") (class "Default")
      (node (ref "U2") (pin "8") (pinfunction "2Y_8") (pintype "bidirectional"))
    )
    (net (code "109") (name "unconnected-(U3-CH-Pad11)") (class "Default")
      (node (ref "U3") (pin "11") (pinfunction "CH_11") (pintype "bidirectional"))
    )
    (net (code "110") (name "unconnected-(U13-IN2-Pad3)") (class "Default")
      (node (ref "U13") (pin "3") (pinfunction "IN2_3") (pintype "bidirectional"))
    )
    (net (code "111") (name "unconnected-(U14-~{MR}-Pad3)") (class "Default")
      (node (ref "U14") (pin "3") (pinfunction "~{MR}_3") (pintype "bidirectional"))
    )
    (net (code "112") (name "unconnected-(U18-CLKB-Pad1)") (class "Default")
      (node (ref "U18") (pin "1") (pinfunction "CLKB_1") (pintype "bidirectional"))
    )
    (net (code "113") (name "unconnected-(U18-DAT-B-Pad15)") (class "Default")
      (node (ref "U18") (pin "15") (pinfunction "DAT-B_15") (pintype "bidirectional"))
    )
    (net (code "114") (name "unconnected-(U18-Q1B-Pad13)") (class "Default")
      (node (ref "U18") (pin "13") (pinfunction "Q1B_13") (pintype "bidirectional"))
    )
    (net (code "115") (name "unconnected-(U18-Q2B-Pad12)") (class "Default")
      (node (ref "U18") (pin "12") (pinfunction "Q2B_12") (pintype "bidirectional"))
    )
    (net (code "116") (name "unconnected-(U18-Q3B-Pad11)") (class "Default")
      (node (ref "U18") (pin "11") (pinfunction "Q3B_11") (pintype "bidirectional"))
    )
    (net (code "117") (name "unconnected-(U18-Q4B-Pad2)") (class "Default")
      (node (ref "U18") (pin "2") (pinfunction "Q4B_2") (pintype "bidirectional"))
    )
    (net (code "118") (name "unconnected-(U18-~{RSTB}-Pad14)") (class "Default")
      (node (ref "U18") (pin "14") (pinfunction "~{RSTB}_14") (pintype "bidirectional"))
    )
  )
)
